# LocalizationBoard_B_1_0_Schematic_CG.net
KiCad netlist of a schematic drawn in Altium Designer
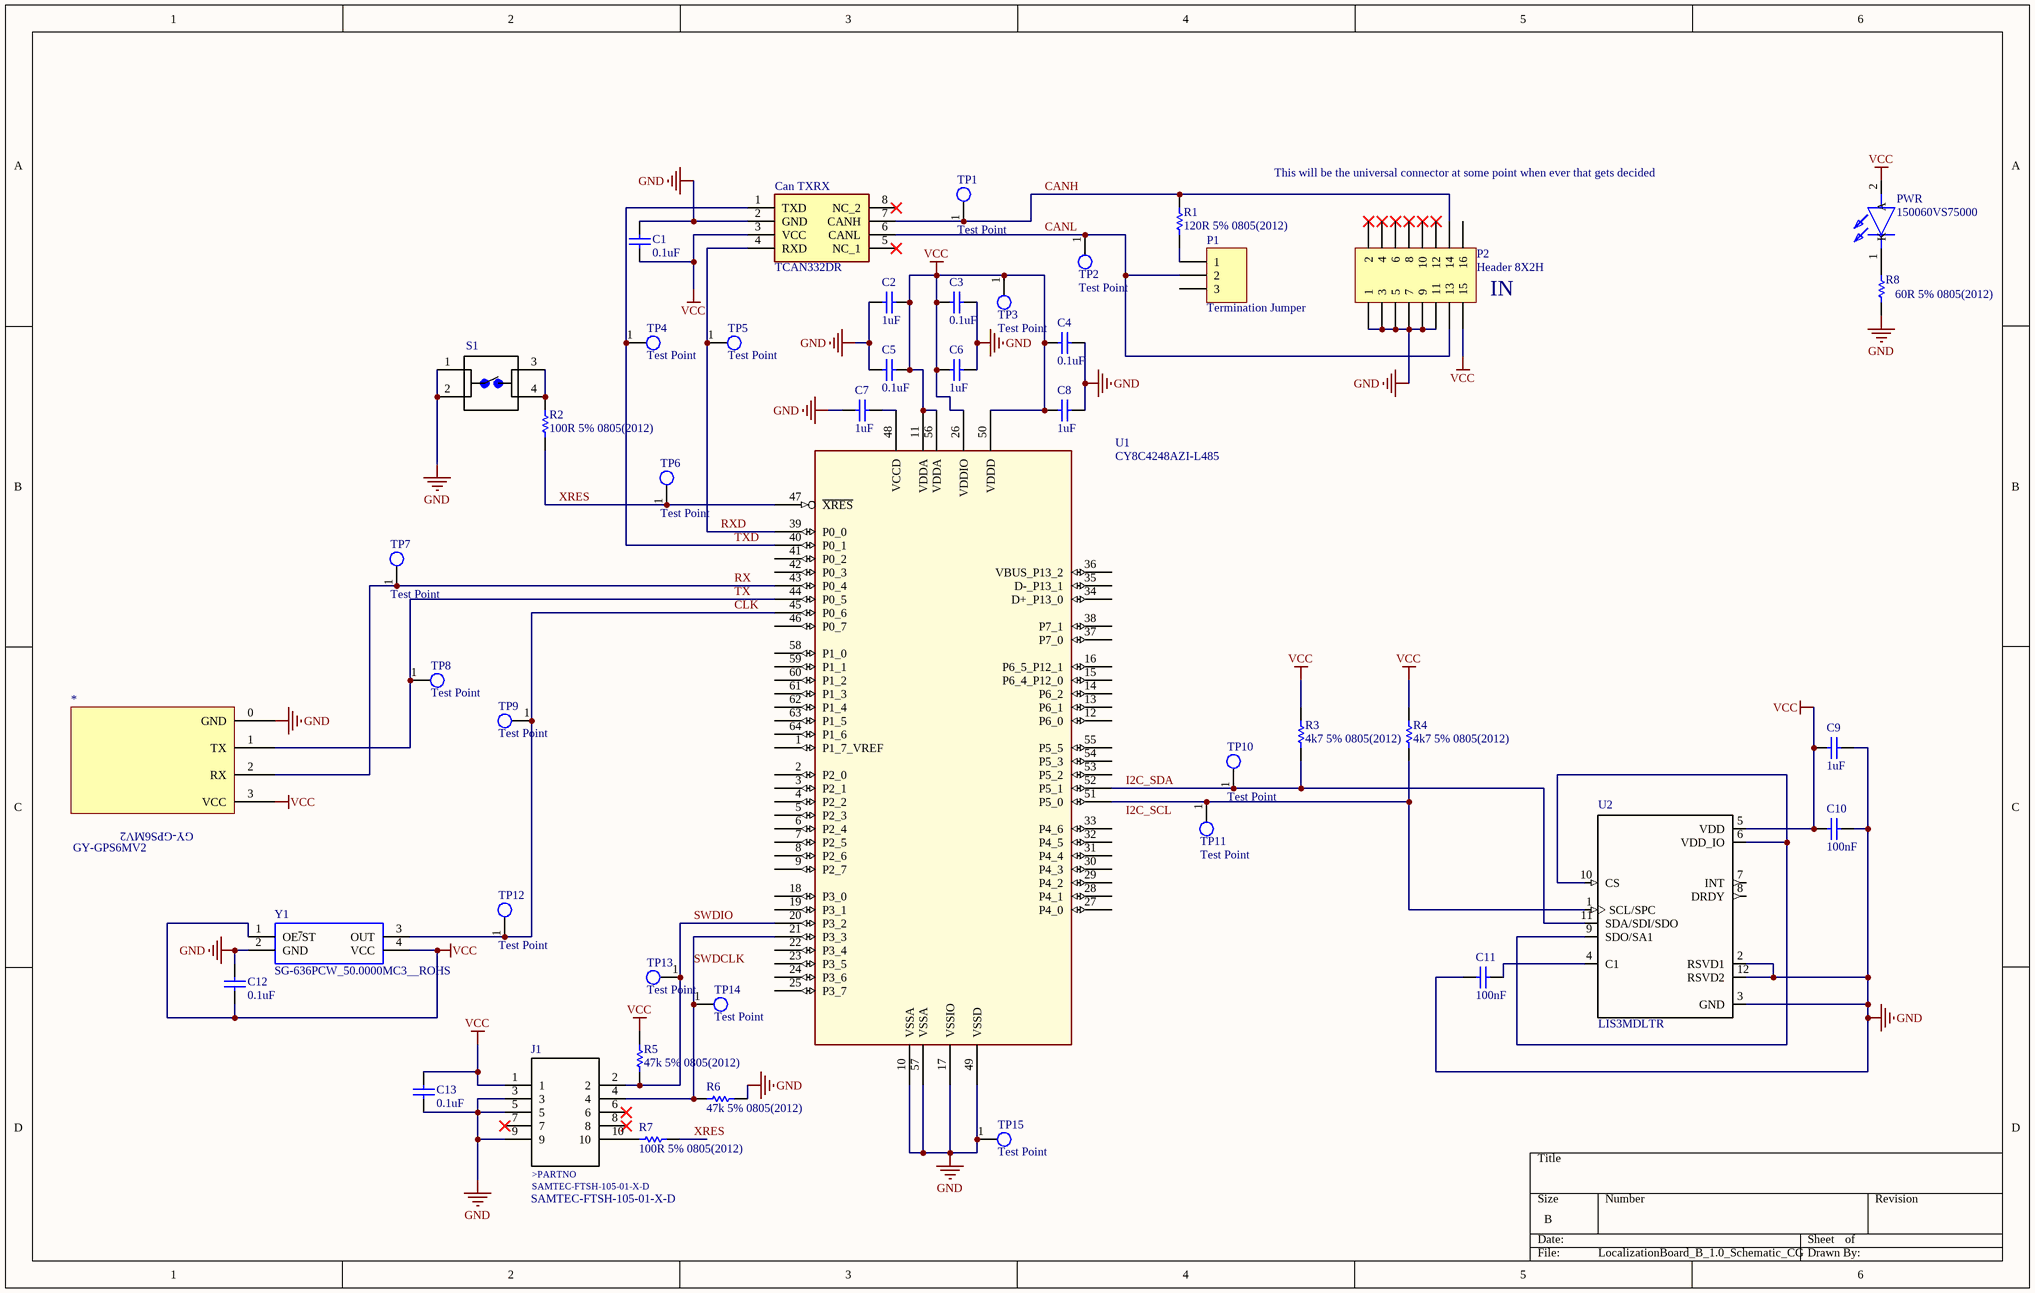
[diagram p0: LocalizationBoard_B_1.0_Schematic_CG.SchDoc]

(export (version "E")
  (design (tool "Eeschema 10.0.6"))
  (components
    (comp (ref "*")
      (value "GY-GPS6MV2")
      (footprint "GY-GPS6MV2")
      (libsource (lib "Husky Robotics Standard Library 2019-2020") (part "GY-GPS6MV2"))
    )
    (comp (ref "C1")
      (value "0.1uF")
      (footprint "CAPC2013X88X50ML20T25")
      (fields (field (name "PART NUMBER") "C0805C222M5RACTU") (field (name "MANUFACTURER") "Kemet"))
      (libsource (lib "Altium Content Vault") (part "CAP"))
    )
    (comp (ref "C2")
      (value "1uF")
      (footprint "CAPC2013X88X50ML20T25")
      (fields (field (name "PART NUMBER") "C0805C222M5RACTU") (field (name "MANUFACTURER") "Kemet"))
      (libsource (lib "Altium Content Vault") (part "CAP"))
    )
    (comp (ref "C3")
      (value "0.1uF")
      (footprint "CAPC2013X88X50ML20T25")
      (fields (field (name "PART NUMBER") "C0805C222M5RACTU") (field (name "MANUFACTURER") "Kemet"))
      (libsource (lib "Altium Content Vault") (part "CAP"))
    )
    (comp (ref "C4")
      (value "0.1uF")
      (footprint "CAPC2013X88X50ML20T25")
      (fields (field (name "PART NUMBER") "C0805C222M5RACTU") (field (name "MANUFACTURER") "Kemet"))
      (libsource (lib "Altium Content Vault") (part "CAP"))
    )
    (comp (ref "C5")
      (value "0.1uF")
      (footprint "CAPC2013X88X50ML20T25")
      (fields (field (name "PART NUMBER") "C0805C222M5RACTU") (field (name "MANUFACTURER") "Kemet"))
      (libsource (lib "Altium Content Vault") (part "CAP"))
    )
    (comp (ref "C6")
      (value "1uF")
      (footprint "CAPC2013X88X50ML20T25")
      (fields (field (name "PART NUMBER") "C0805C222M5RACTU") (field (name "MANUFACTURER") "Kemet"))
      (libsource (lib "Altium Content Vault") (part "CAP"))
    )
    (comp (ref "C7")
      (value "1uF")
      (footprint "CAPC2013X88X50ML20T25")
      (fields (field (name "PART NUMBER") "C0805C222M5RACTU") (field (name "MANUFACTURER") "Kemet"))
      (libsource (lib "Altium Content Vault") (part "CAP"))
    )
    (comp (ref "C8")
      (value "1uF")
      (footprint "CAPC2013X88X50ML20T25")
      (fields (field (name "PART NUMBER") "C0805C222M5RACTU") (field (name "MANUFACTURER") "Kemet"))
      (libsource (lib "Altium Content Vault") (part "CAP"))
    )
    (comp (ref "C9")
      (value "1uF")
      (footprint "CAPC2013X88X50ML20T25")
      (fields (field (name "PART NUMBER") "C0805C222M5RACTU") (field (name "MANUFACTURER") "Kemet"))
      (libsource (lib "Altium Content Vault") (part "CAP"))
    )
    (comp (ref "C10")
      (value "100nF")
      (footprint "CAPC2013X88X50ML20T25")
      (fields (field (name "PART NUMBER") "C0805C222M5RACTU") (field (name "MANUFACTURER") "Kemet"))
      (libsource (lib "Altium Content Vault") (part "CAP"))
    )
    (comp (ref "C11")
      (value "100nF")
      (footprint "CAPC2013X88X50ML20T25")
      (fields (field (name "PART NUMBER") "C0805C222M5RACTU") (field (name "MANUFACTURER") "Kemet"))
      (libsource (lib "Altium Content Vault") (part "CAP"))
    )
    (comp (ref "C12")
      (value "0.1uF")
      (footprint "CAPC2013X88X50ML20T25")
      (fields (field (name "PART NUMBER") "C0805C222M5RACTU") (field (name "MANUFACTURER") "Kemet"))
      (libsource (lib "Altium Content Vault") (part "CAP"))
    )
    (comp (ref "C13")
      (value "0.1uF")
      (footprint "CAPC2013X88X50ML20T25")
      (fields (field (name "PART NUMBER") "C0805C222M5RACTU") (field (name "MANUFACTURER") "Kemet"))
      (libsource (lib "Altium Content Vault") (part "CAP"))
    )
    (comp (ref "Can TXRX")
      (value "TCAN332DR")
      (footprint "SamacSys:SOIC127P600X175-8N")
      (description "Integrated Circuit")
      (fields (field (name "MOUSER PART NUMBER") "595-TCAN332DR"))
      (libsource (lib "*") (part "TCAN332DR"))
    )
    (comp (ref "J1")
      (value "SAMTEC-FTSH-105-01-X-D")
      (footprint "SAMTEC-FTSH-105-01-X-D")
      (libsource (lib "Husky Robotics Standard Library 2019-2020") (part "SAMTEC-FTSH-105-01-X-D"))
    )
    (comp (ref "P1")
      (value "Termination Jumper")
      (footprint "HDR1X3")
      (description "Header, 3-Pin")
      (fields (field (name "PUBLISHER") "Altium Limited"))
      (libsource (lib "Miscellaneous Connectors") (part "Header 3"))
    )
    (comp (ref "P2")
      (value "Header 8X2H")
      (footprint "HDR2X8H")
      (description "Header, 8-Pin, Dual row, Right Angle")
      (fields (field (name "PUBLISHER") "Altium Limited"))
      (libsource (lib "Miscellaneous Connectors") (part "Header 8X2H"))
    )
    (comp (ref "PWR")
      (value "150060VS75000")
      (footprint "SamacSys:LEDC1608X80N")
      (description "LED")
      (fields
        (field (name "MOUSER PART NUMBER") "710-150060VS75000")
        (field (name "RS PART NUMBER") "8154215P")
      )
      (libsource (lib "*") (part "150060VS75000"))
    )
    (comp (ref "R1")
      (value "120R 5% 0805(2012)")
      (footprint "RESC0805(2012)_N")
      (description "120R 0.125W 5% 0805 (2012 Metric)  SMD")
      (fields (field (name "TOLERANCE") "5 %") (field (name "POWER") "0.125 W"))
      (libsource (lib "Husky Robotics Standard Library 2019-2020") (part "120R 5% 0805"))
    )
    (comp (ref "R2")
      (value "100R 5% 0805(2012)")
      (footprint "RESC0805(2012)_N")
      (description "120R 0.125W 5% 0805 (2012 Metric)  SMD")
      (fields (field (name "TOLERANCE") "5 %") (field (name "POWER") "0.125 W"))
      (libsource (lib "Husky Robotics Standard Library 2019-2020") (part "120R 5% 0805"))
    )
    (comp (ref "R3")
      (value "4k7 5% 0805(2012)")
      (footprint "RESC0805(2012)_N")
      (description "120R 0.125W 5% 0805 (2012 Metric)  SMD")
      (fields (field (name "TOLERANCE") "5 %") (field (name "POWER") "0.125 W"))
      (libsource (lib "Husky Robotics Standard Library 2019-2020") (part "120R 5% 0805"))
    )
    (comp (ref "R4")
      (value "4k7 5% 0805(2012)")
      (footprint "RESC0805(2012)_N")
      (description "120R 0.125W 5% 0805 (2012 Metric)  SMD")
      (fields (field (name "TOLERANCE") "5 %") (field (name "POWER") "0.125 W"))
      (libsource (lib "Husky Robotics Standard Library 2019-2020") (part "120R 5% 0805"))
    )
    (comp (ref "R5")
      (value "47k 5% 0805(2012)")
      (footprint "RESC0805(2012)_N")
      (description "120R 0.125W 5% 0805 (2012 Metric)  SMD")
      (fields (field (name "TOLERANCE") "5 %") (field (name "POWER") "0.125 W"))
      (libsource (lib "Husky Robotics Standard Library 2019-2020") (part "120R 5% 0805"))
    )
    (comp (ref "R6")
      (value "47k 5% 0805(2012)")
      (footprint "RESC0805(2012)_N")
      (description "120R 0.125W 5% 0805 (2012 Metric)  SMD")
      (fields (field (name "TOLERANCE") "5 %") (field (name "POWER") "0.125 W"))
      (libsource (lib "Husky Robotics Standard Library 2019-2020") (part "120R 5% 0805"))
    )
    (comp (ref "R7")
      (value "100R 5% 0805(2012)")
      (footprint "RESC0805(2012)_N")
      (description "120R 0.125W 5% 0805 (2012 Metric)  SMD")
      (fields (field (name "TOLERANCE") "5 %") (field (name "POWER") "0.125 W"))
      (libsource (lib "Husky Robotics Standard Library 2019-2020") (part "120R 5% 0805"))
    )
    (comp (ref "R8")
      (value "60R 5% 0805(2012)")
      (footprint "RESC0805(2012)_N")
      (description "120R 0.125W 5% 0805 (2012 Metric)  SMD")
      (fields (field (name "TOLERANCE") "5 %") (field (name "POWER") "0.125 W"))
      (libsource (lib "Husky Robotics Standard Library 2019-2020") (part "120R 5% 0805"))
    )
    (comp (ref "S1")
      (value "1825910-7")
      (footprint "Switch 6mm 24V (NO)")
      (description "FSM4JAH=6MM TACT SWITCH, HIGH TEMP")
      (fields (field (name "MF") "TE Connectivity") (field (name "DIGI-KEY_PART_NUMBER") "450-1804-ND"))
      (libsource (lib "Husky Robotics Standard Library 2019-2020") (part "Switch 6mm 24V (NO)"))
    )
    (comp (ref "TP1")
      (value "Test Point")
      (footprint "Test Point Through-hole")
      (libsource (lib "Husky Robotics Standard Library 2019-2020") (part "Test Point"))
    )
    (comp (ref "TP2")
      (value "Test Point")
      (footprint "Test Point Through-hole")
      (libsource (lib "Husky Robotics Standard Library 2019-2020") (part "Test Point"))
    )
    (comp (ref "TP3")
      (value "Test Point")
      (footprint "Test Point Through-hole")
      (libsource (lib "Husky Robotics Standard Library 2019-2020") (part "Test Point"))
    )
    (comp (ref "TP4")
      (value "Test Point")
      (footprint "Test Point Through-hole")
      (libsource (lib "Husky Robotics Standard Library 2019-2020") (part "Test Point"))
    )
    (comp (ref "TP5")
      (value "Test Point")
      (footprint "Test Point Through-hole")
      (libsource (lib "Husky Robotics Standard Library 2019-2020") (part "Test Point"))
    )
    (comp (ref "TP6")
      (value "Test Point")
      (footprint "Test Point Through-hole")
      (libsource (lib "Husky Robotics Standard Library 2019-2020") (part "Test Point"))
    )
    (comp (ref "TP7")
      (value "Test Point")
      (footprint "Test Point Through-hole")
      (libsource (lib "Husky Robotics Standard Library 2019-2020") (part "Test Point"))
    )
    (comp (ref "TP8")
      (value "Test Point")
      (footprint "Test Point Through-hole")
      (libsource (lib "Husky Robotics Standard Library 2019-2020") (part "Test Point"))
    )
    (comp (ref "TP9")
      (value "Test Point")
      (footprint "Test Point Through-hole")
      (libsource (lib "Husky Robotics Standard Library 2019-2020") (part "Test Point"))
    )
    (comp (ref "TP10")
      (value "Test Point")
      (footprint "Test Point Through-hole")
      (libsource (lib "Husky Robotics Standard Library 2019-2020") (part "Test Point"))
    )
    (comp (ref "TP11")
      (value "Test Point")
      (footprint "Test Point Through-hole")
      (libsource (lib "Husky Robotics Standard Library 2019-2020") (part "Test Point"))
    )
    (comp (ref "TP12")
      (value "Test Point")
      (footprint "Test Point Through-hole")
      (libsource (lib "Husky Robotics Standard Library 2019-2020") (part "Test Point"))
    )
    (comp (ref "TP13")
      (value "Test Point")
      (footprint "Test Point Through-hole")
      (libsource (lib "Husky Robotics Standard Library 2019-2020") (part "Test Point"))
    )
    (comp (ref "TP14")
      (value "Test Point")
      (footprint "Test Point Through-hole")
      (libsource (lib "Husky Robotics Standard Library 2019-2020") (part "Test Point"))
    )
    (comp (ref "TP15")
      (value "Test Point")
      (footprint "Test Point Through-hole")
      (libsource (lib "Husky Robotics Standard Library 2019-2020") (part "Test Point"))
    )
    (comp (ref "U1")
      (value "CY8C4248AZI-L485")
      (footprint "TQFP50P1200X1200X160-64N")
      (libsource (lib "Husky Robotics Standard Library 2019-2020") (part "CY8C4248AZI-L485"))
    )
    (comp (ref "U2")
      (value "LIS3MDLTR")
      (footprint "*XDCR_LIS3MDLTR")
      (description "LIS3MDL Series 3 Axis Â±2/Â±8/Â±12/Â±16 g 3.6V High Performance Magnetometer LGA-12")
      (fields (field (name "DIGI-KEY_PART_NUMBER") "497-13892-1-ND") (field (name "MF") "STMicroelectronics"))
      (libsource (lib "LIS3MDLTR") (part "LIS3MDLTR"))
    )
    (comp (ref "Y1")
      (value "SG-636PCW_50.0000MC3__ROHS")
      (footprint "SG-636")
      (description "Standard Clock Oscillators 50MHz 3.3Volt 100ppm -20C +70C")
      (fields (field (name "MANUFACTURER_PART_NUMBER") "SG-636PCW 50.0000MC3: ROHS"))
      (libsource (lib "Husky Robotics Standard Library 2019-2020") (part "SG-636"))
    )
  )
  (nets
    (net (code "1") (name "/CANH") (class "Default")
      (node (ref "Can TXRX") (pin "7") (pinfunction "CANH_7") (pintype "passive"))
      (node (ref "P2") (pin "14") (pinfunction "14_14") (pintype "passive"))
      (node (ref "R1") (pin "2") (pinfunction "2_2") (pintype "passive"))
      (node (ref "TP1") (pin "1") (pinfunction "1_1") (pintype "passive"))
    )
    (net (code "2") (name "/CANL") (class "Default")
      (node (ref "Can TXRX") (pin "6") (pinfunction "CANL_6") (pintype "passive"))
      (node (ref "P1") (pin "2") (pinfunction "2_2") (pintype "passive"))
      (node (ref "P2") (pin "13") (pinfunction "13_13") (pintype "passive"))
      (node (ref "TP2") (pin "1") (pinfunction "1_1") (pintype "passive"))
    )
    (net (code "3") (name "/CLK") (class "Default")
      (node (ref "TP12") (pin "1") (pinfunction "1_1") (pintype "passive"))
      (node (ref "TP9") (pin "1") (pinfunction "1_1") (pintype "passive"))
      (node (ref "U1") (pin "45") (pinfunction "P0_6_45") (pintype "bidirectional"))
      (node (ref "Y1") (pin "3") (pinfunction "OUT_3") (pintype "passive"))
    )
    (net (code "4") (name "/I2C_SCL") (class "Default")
      (node (ref "R4") (pin "1") (pinfunction "1_1") (pintype "passive"))
      (node (ref "TP11") (pin "1") (pinfunction "1_1") (pintype "passive"))
      (node (ref "U1") (pin "51") (pinfunction "P5_0_51") (pintype "bidirectional"))
      (node (ref "U2") (pin "1") (pinfunction "SCL/SPC_1") (pintype "input"))
    )
    (net (code "5") (name "/I2C_SDA") (class "Default")
      (node (ref "R3") (pin "1") (pinfunction "1_1") (pintype "passive"))
      (node (ref "TP10") (pin "1") (pinfunction "1_1") (pintype "passive"))
      (node (ref "U1") (pin "52") (pinfunction "P5_1_52") (pintype "bidirectional"))
      (node (ref "U2") (pin "11") (pinfunction "SDA/SDI/SDO_11") (pintype "bidirectional"))
    )
    (net (code "6") (name "/RX") (class "Default")
      (node (ref "*") (pin "2") (pinfunction "RX_2") (pintype "passive"))
      (node (ref "TP7") (pin "1") (pinfunction "1_1") (pintype "passive"))
      (node (ref "U1") (pin "43") (pinfunction "P0_4_43") (pintype "bidirectional"))
    )
    (net (code "7") (name "/RXD") (class "Default")
      (node (ref "Can TXRX") (pin "4") (pinfunction "RXD_4") (pintype "passive"))
      (node (ref "TP5") (pin "1") (pinfunction "1_1") (pintype "passive"))
      (node (ref "U1") (pin "39") (pinfunction "P0_0_39") (pintype "bidirectional"))
    )
    (net (code "8") (name "/SWDCLK") (class "Default")
      (node (ref "J1") (pin "4") (pinfunction "4_4") (pintype "passive"))
      (node (ref "R6") (pin "1") (pinfunction "1_1") (pintype "passive"))
      (node (ref "TP14") (pin "1") (pinfunction "1_1") (pintype "passive"))
      (node (ref "U1") (pin "21") (pinfunction "P3_3_21") (pintype "bidirectional"))
    )
    (net (code "9") (name "/SWDIO") (class "Default")
      (node (ref "J1") (pin "2") (pinfunction "2_2") (pintype "passive"))
      (node (ref "R5") (pin "1") (pinfunction "1_1") (pintype "passive"))
      (node (ref "TP13") (pin "1") (pinfunction "1_1") (pintype "passive"))
      (node (ref "U1") (pin "20") (pinfunction "P3_2_20") (pintype "bidirectional"))
    )
    (net (code "10") (name "/TX") (class "Default")
      (node (ref "*") (pin "1") (pinfunction "TX_1") (pintype "passive"))
      (node (ref "TP8") (pin "1") (pinfunction "1_1") (pintype "passive"))
      (node (ref "U1") (pin "44") (pinfunction "P0_5_44") (pintype "bidirectional"))
    )
    (net (code "11") (name "/TXD") (class "Default")
      (node (ref "Can TXRX") (pin "1") (pinfunction "TXD_1") (pintype "passive"))
      (node (ref "TP4") (pin "1") (pinfunction "1_1") (pintype "passive"))
      (node (ref "U1") (pin "40") (pinfunction "P0_1_40") (pintype "bidirectional"))
    )
    (net (code "12") (name "/XRES") (class "Default")
      (node (ref "R2") (pin "1") (pinfunction "1_1") (pintype "passive"))
      (node (ref "R7") (pin "1") (pinfunction "1_1") (pintype "passive"))
      (node (ref "TP6") (pin "1") (pinfunction "1_1") (pintype "passive"))
      (node (ref "U1") (pin "47") (pinfunction "~{XRES}_47") (pintype "input"))
    )
    (net (code "13") (name "GND") (class "Default")
      (node (ref "*") (pin "0") (pinfunction "GND_0") (pintype "passive"))
      (node (ref "C1") (pin "2") (pinfunction "2_2") (pintype "passive"))
      (node (ref "C10") (pin "2") (pinfunction "2_2") (pintype "passive"))
      (node (ref "C11") (pin "1") (pinfunction "1_1") (pintype "passive"))
      (node (ref "C12") (pin "2") (pinfunction "2_2") (pintype "passive"))
      (node (ref "C13") (pin "2") (pinfunction "2_2") (pintype "passive"))
      (node (ref "C2") (pin "1") (pinfunction "1_1") (pintype "passive"))
      (node (ref "C3") (pin "2") (pinfunction "2_2") (pintype "passive"))
      (node (ref "C4") (pin "2") (pinfunction "2_2") (pintype "passive"))
      (node (ref "C5") (pin "1") (pinfunction "1_1") (pintype "passive"))
      (node (ref "C6") (pin "2") (pinfunction "2_2") (pintype "passive"))
      (node (ref "C7") (pin "1") (pinfunction "1_1") (pintype "passive"))
      (node (ref "C8") (pin "2") (pinfunction "2_2") (pintype "passive"))
      (node (ref "C9") (pin "2") (pinfunction "2_2") (pintype "passive"))
      (node (ref "Can TXRX") (pin "2") (pinfunction "GND_2") (pintype "passive"))
      (node (ref "J1") (pin "3") (pinfunction "3_3") (pintype "passive"))
      (node (ref "J1") (pin "5") (pinfunction "5_5") (pintype "passive"))
      (node (ref "J1") (pin "9") (pinfunction "9_9") (pintype "passive"))
      (node (ref "P2") (pin "1") (pinfunction "1_1") (pintype "passive"))
      (node (ref "P2") (pin "11") (pinfunction "11_11") (pintype "passive"))
      (node (ref "P2") (pin "3") (pinfunction "3_3") (pintype "passive"))
      (node (ref "P2") (pin "5") (pinfunction "5_5") (pintype "passive"))
      (node (ref "P2") (pin "7") (pinfunction "7_7") (pintype "passive"))
      (node (ref "P2") (pin "9") (pinfunction "9_9") (pintype "passive"))
      (node (ref "R6") (pin "2") (pinfunction "2_2") (pintype "passive"))
      (node (ref "R8") (pin "1") (pinfunction "1_1") (pintype "passive"))
      (node (ref "S1") (pin "1") (pinfunction "1_1") (pintype "passive"))
      (node (ref "S1") (pin "2") (pinfunction "2_2") (pintype "passive"))
      (node (ref "TP15") (pin "1") (pinfunction "1_1") (pintype "passive"))
      (node (ref "U1") (pin "10") (pinfunction "VSSA_10") (pintype "power_in"))
      (node (ref "U1") (pin "17") (pinfunction "VSSIO_17") (pintype "power_in"))
      (node (ref "U1") (pin "49") (pinfunction "VSSD_49") (pintype "power_in"))
      (node (ref "U1") (pin "57") (pinfunction "VSSA_57") (pintype "power_in"))
      (node (ref "U2") (pin "12") (pinfunction "RSVD2_12") (pintype "passive"))
      (node (ref "U2") (pin "2") (pinfunction "RSVD1_2") (pintype "passive"))
      (node (ref "U2") (pin "3") (pinfunction "GND_3") (pintype "power_in"))
      (node (ref "Y1") (pin "2") (pinfunction "GND_2") (pintype "passive"))
    )
    (net (code "14") (name "Net-(J1-Pad10)") (class "Default")
      (node (ref "J1") (pin "10") (pinfunction "10_10") (pintype "passive"))
      (node (ref "R7") (pin "2") (pinfunction "2_2") (pintype "passive"))
    )
    (net (code "15") (name "Net-(P1-Pad1)") (class "Default")
      (node (ref "P1") (pin "1") (pinfunction "1_1") (pintype "passive"))
      (node (ref "R1") (pin "1") (pinfunction "1_1") (pintype "passive"))
    )
    (net (code "16") (name "Net-(PWR-K)") (class "Default")
      (node (ref "PWR") (pin "1") (pinfunction "K_1") (pintype "passive"))
      (node (ref "R8") (pin "2") (pinfunction "2_2") (pintype "passive"))
    )
    (net (code "17") (name "Net-(R2-Pad2)") (class "Default")
      (node (ref "R2") (pin "2") (pinfunction "2_2") (pintype "passive"))
      (node (ref "S1") (pin "3") (pinfunction "3_3") (pintype "passive"))
      (node (ref "S1") (pin "4") (pinfunction "4_4") (pintype "passive"))
    )
    (net (code "18") (name "Net-(U1-VCCD)") (class "Default")
      (node (ref "C7") (pin "2") (pinfunction "2_2") (pintype "passive"))
      (node (ref "U1") (pin "48") (pinfunction "VCCD_48") (pintype "power_in"))
    )
    (net (code "19") (name "Net-(U2-C1)") (class "Default")
      (node (ref "C11") (pin "2") (pinfunction "2_2") (pintype "passive"))
      (node (ref "U2") (pin "4") (pinfunction "C1_4") (pintype "passive"))
    )
    (net (code "20") (name "Net-(U2-CS)") (class "Default")
      (node (ref "U2") (pin "10") (pinfunction "CS_10") (pintype "input"))
      (node (ref "U2") (pin "6") (pinfunction "VDD_IO_6") (pintype "power_in"))
      (node (ref "U2") (pin "9") (pinfunction "SDO/SA1_9") (pintype "bidirectional"))
    )
    (net (code "21") (name "VCC") (class "Default")
      (node (ref "*") (pin "3") (pinfunction "VCC_3") (pintype "passive"))
      (node (ref "C1") (pin "1") (pinfunction "1_1") (pintype "passive"))
      (node (ref "C10") (pin "1") (pinfunction "1_1") (pintype "passive"))
      (node (ref "C12") (pin "1") (pinfunction "1_1") (pintype "passive"))
      (node (ref "C13") (pin "1") (pinfunction "1_1") (pintype "passive"))
      (node (ref "C2") (pin "2") (pinfunction "2_2") (pintype "passive"))
      (node (ref "C3") (pin "1") (pinfunction "1_1") (pintype "passive"))
      (node (ref "C4") (pin "1") (pinfunction "1_1") (pintype "passive"))
      (node (ref "C5") (pin "2") (pinfunction "2_2") (pintype "passive"))
      (node (ref "C6") (pin "1") (pinfunction "1_1") (pintype "passive"))
      (node (ref "C8") (pin "1") (pinfunction "1_1") (pintype "passive"))
      (node (ref "C9") (pin "1") (pinfunction "1_1") (pintype "passive"))
      (node (ref "Can TXRX") (pin "3") (pinfunction "VCC_3") (pintype "passive"))
      (node (ref "J1") (pin "1") (pinfunction "1_1") (pintype "passive"))
      (node (ref "P2") (pin "15") (pinfunction "15_15") (pintype "passive"))
      (node (ref "PWR") (pin "2") (pinfunction "A_2") (pintype "passive"))
      (node (ref "R3") (pin "2") (pinfunction "2_2") (pintype "passive"))
      (node (ref "R4") (pin "2") (pinfunction "2_2") (pintype "passive"))
      (node (ref "R5") (pin "2") (pinfunction "2_2") (pintype "passive"))
      (node (ref "TP3") (pin "1") (pinfunction "1_1") (pintype "passive"))
      (node (ref "U1") (pin "11") (pinfunction "VDDA_11") (pintype "power_in"))
      (node (ref "U1") (pin "26") (pinfunction "VDDIO_26") (pintype "power_in"))
      (node (ref "U1") (pin "50") (pinfunction "VDDD_50") (pintype "power_in"))
      (node (ref "U1") (pin "56") (pinfunction "VDDA_56") (pintype "power_in"))
      (node (ref "U2") (pin "5") (pinfunction "VDD_5") (pintype "power_in"))
      (node (ref "Y1") (pin "1") (pinfunction "OE~{/}ST_1") (pintype "passive"))
      (node (ref "Y1") (pin "4") (pinfunction "VCC_4") (pintype "power_in"))
    )
    (net (code "22") (name "unconnected-(Can TXRX-NC_1-Pad5)") (class "Default")
      (node (ref "Can TXRX") (pin "5") (pinfunction "NC_1_5") (pintype "passive+no_connect"))
    )
    (net (code "23") (name "unconnected-(Can TXRX-NC_2-Pad8)") (class "Default")
      (node (ref "Can TXRX") (pin "8") (pinfunction "NC_2_8") (pintype "passive+no_connect"))
    )
    (net (code "24") (name "unconnected-(J1-Pad6)") (class "Default")
      (node (ref "J1") (pin "6") (pinfunction "6_6") (pintype "passive+no_connect"))
    )
    (net (code "25") (name "unconnected-(J1-Pad7)") (class "Default")
      (node (ref "J1") (pin "7") (pinfunction "7_7") (pintype "passive+no_connect"))
    )
    (net (code "26") (name "unconnected-(J1-Pad8)") (class "Default")
      (node (ref "J1") (pin "8") (pinfunction "8_8") (pintype "passive+no_connect"))
    )
    (net (code "27") (name "unconnected-(P1-Pad3)") (class "Default")
      (node (ref "P1") (pin "3") (pinfunction "3_3") (pintype "passive"))
    )
    (net (code "28") (name "unconnected-(P2-Pad2)") (class "Default")
      (node (ref "P2") (pin "2") (pinfunction "2_2") (pintype "passive+no_connect"))
    )
    (net (code "29") (name "unconnected-(P2-Pad4)") (class "Default")
      (node (ref "P2") (pin "4") (pinfunction "4_4") (pintype "passive+no_connect"))
    )
    (net (code "30") (name "unconnected-(P2-Pad6)") (class "Default")
      (node (ref "P2") (pin "6") (pinfunction "6_6") (pintype "passive+no_connect"))
    )
    (net (code "31") (name "unconnected-(P2-Pad8)") (class "Default")
      (node (ref "P2") (pin "8") (pinfunction "8_8") (pintype "passive+no_connect"))
    )
    (net (code "32") (name "unconnected-(P2-Pad10)") (class "Default")
      (node (ref "P2") (pin "10") (pinfunction "10_10") (pintype "passive+no_connect"))
    )
    (net (code "33") (name "unconnected-(P2-Pad12)") (class "Default")
      (node (ref "P2") (pin "12") (pinfunction "12_12") (pintype "passive+no_connect"))
    )
    (net (code "34") (name "unconnected-(P2-Pad16)") (class "Default")
      (node (ref "P2") (pin "16") (pinfunction "16_16") (pintype "passive"))
    )
    (net (code "35") (name "unconnected-(U1-D+_P13_0-Pad34)") (class "Default")
      (node (ref "U1") (pin "34") (pinfunction "D+_P13_0_34") (pintype "bidirectional"))
    )
    (net (code "36") (name "unconnected-(U1-D-_P13_1-Pad35)") (class "Default")
      (node (ref "U1") (pin "35") (pinfunction "D-_P13_1_35") (pintype "bidirectional"))
    )
    (net (code "37") (name "unconnected-(U1-P0_2-Pad41)") (class "Default")
      (node (ref "U1") (pin "41") (pinfunction "P0_2_41") (pintype "bidirectional"))
    )
    (net (code "38") (name "unconnected-(U1-P0_3-Pad42)") (class "Default")
      (node (ref "U1") (pin "42") (pinfunction "P0_3_42") (pintype "bidirectional"))
    )
    (net (code "39") (name "unconnected-(U1-P0_7-Pad46)") (class "Default")
      (node (ref "U1") (pin "46") (pinfunction "P0_7_46") (pintype "bidirectional"))
    )
    (net (code "40") (name "unconnected-(U1-P1_0-Pad58)") (class "Default")
      (node (ref "U1") (pin "58") (pinfunction "P1_0_58") (pintype "bidirectional"))
    )
    (net (code "41") (name "unconnected-(U1-P1_1-Pad59)") (class "Default")
      (node (ref "U1") (pin "59") (pinfunction "P1_1_59") (pintype "bidirectional"))
    )
    (net (code "42") (name "unconnected-(U1-P1_2-Pad60)") (class "Default")
      (node (ref "U1") (pin "60") (pinfunction "P1_2_60") (pintype "bidirectional"))
    )
    (net (code "43") (name "unconnected-(U1-P1_3-Pad61)") (class "Default")
      (node (ref "U1") (pin "61") (pinfunction "P1_3_61") (pintype "bidirectional"))
    )
    (net (code "44") (name "unconnected-(U1-P1_4-Pad62)") (class "Default")
      (node (ref "U1") (pin "62") (pinfunction "P1_4_62") (pintype "bidirectional"))
    )
    (net (code "45") (name "unconnected-(U1-P1_5-Pad63)") (class "Default")
      (node (ref "U1") (pin "63") (pinfunction "P1_5_63") (pintype "bidirectional"))
    )
    (net (code "46") (name "unconnected-(U1-P1_6-Pad64)") (class "Default")
      (node (ref "U1") (pin "64") (pinfunction "P1_6_64") (pintype "bidirectional"))
    )
    (net (code "47") (name "unconnected-(U1-P1_7_VREF-Pad1)") (class "Default")
      (node (ref "U1") (pin "1") (pinfunction "P1_7_VREF_1") (pintype "bidirectional"))
    )
    (net (code "48") (name "unconnected-(U1-P2_0-Pad2)") (class "Default")
      (node (ref "U1") (pin "2") (pinfunction "P2_0_2") (pintype "bidirectional"))
    )
    (net (code "49") (name "unconnected-(U1-P2_1-Pad3)") (class "Default")
      (node (ref "U1") (pin "3") (pinfunction "P2_1_3") (pintype "bidirectional"))
    )
    (net (code "50") (name "unconnected-(U1-P2_2-Pad4)") (class "Default")
      (node (ref "U1") (pin "4") (pinfunction "P2_2_4") (pintype "bidirectional"))
    )
    (net (code "51") (name "unconnected-(U1-P2_3-Pad5)") (class "Default")
      (node (ref "U1") (pin "5") (pinfunction "P2_3_5") (pintype "bidirectional"))
    )
    (net (code "52") (name "unconnected-(U1-P2_4-Pad6)") (class "Default")
      (node (ref "U1") (pin "6") (pinfunction "P2_4_6") (pintype "bidirectional"))
    )
    (net (code "53") (name "unconnected-(U1-P2_5-Pad7)") (class "Default")
      (node (ref "U1") (pin "7") (pinfunction "P2_5_7") (pintype "bidirectional"))
    )
    (net (code "54") (name "unconnected-(U1-P2_6-Pad8)") (class "Default")
      (node (ref "U1") (pin "8") (pinfunction "P2_6_8") (pintype "bidirectional"))
    )
    (net (code "55") (name "unconnected-(U1-P2_7-Pad9)") (class "Default")
      (node (ref "U1") (pin "9") (pinfunction "P2_7_9") (pintype "bidirectional"))
    )
    (net (code "56") (name "unconnected-(U1-P3_0-Pad18)") (class "Default")
      (node (ref "U1") (pin "18") (pinfunction "P3_0_18") (pintype "bidirectional"))
    )
    (net (code "57") (name "unconnected-(U1-P3_1-Pad19)") (class "Default")
      (node (ref "U1") (pin "19") (pinfunction "P3_1_19") (pintype "bidirectional"))
    )
    (net (code "58") (name "unconnected-(U1-P3_4-Pad22)") (class "Default")
      (node (ref "U1") (pin "22") (pinfunction "P3_4_22") (pintype "bidirectional"))
    )
    (net (code "59") (name "unconnected-(U1-P3_5-Pad23)") (class "Default")
      (node (ref "U1") (pin "23") (pinfunction "P3_5_23") (pintype "bidirectional"))
    )
    (net (code "60") (name "unconnected-(U1-P3_6-Pad24)") (class "Default")
      (node (ref "U1") (pin "24") (pinfunction "P3_6_24") (pintype "bidirectional"))
    )
    (net (code "61") (name "unconnected-(U1-P3_7-Pad25)") (class "Default")
      (node (ref "U1") (pin "25") (pinfunction "P3_7_25") (pintype "bidirectional"))
    )
    (net (code "62") (name "unconnected-(U1-P4_0-Pad27)") (class "Default")
      (node (ref "U1") (pin "27") (pinfunction "P4_0_27") (pintype "bidirectional"))
    )
    (net (code "63") (name "unconnected-(U1-P4_1-Pad28)") (class "Default")
      (node (ref "U1") (pin "28") (pinfunction "P4_1_28") (pintype "bidirectional"))
    )
    (net (code "64") (name "unconnected-(U1-P4_2-Pad29)") (class "Default")
      (node (ref "U1") (pin "29") (pinfunction "P4_2_29") (pintype "bidirectional"))
    )
    (net (code "65") (name "unconnected-(U1-P4_3-Pad30)") (class "Default")
      (node (ref "U1") (pin "30") (pinfunction "P4_3_30") (pintype "bidirectional"))
    )
    (net (code "66") (name "unconnected-(U1-P4_4-Pad31)") (class "Default")
      (node (ref "U1") (pin "31") (pinfunction "P4_4_31") (pintype "bidirectional"))
    )
    (net (code "67") (name "unconnected-(U1-P4_5-Pad32)") (class "Default")
      (node (ref "U1") (pin "32") (pinfunction "P4_5_32") (pintype "bidirectional"))
    )
    (net (code "68") (name "unconnected-(U1-P4_6-Pad33)") (class "Default")
      (node (ref "U1") (pin "33") (pinfunction "P4_6_33") (pintype "bidirectional"))
    )
    (net (code "69") (name "unconnected-(U1-P5_2-Pad53)") (class "Default")
      (node (ref "U1") (pin "53") (pinfunction "P5_2_53") (pintype "bidirectional"))
    )
    (net (code "70") (name "unconnected-(U1-P5_3-Pad54)") (class "Default")
      (node (ref "U1") (pin "54") (pinfunction "P5_3_54") (pintype "bidirectional"))
    )
    (net (code "71") (name "unconnected-(U1-P5_5-Pad55)") (class "Default")
      (node (ref "U1") (pin "55") (pinfunction "P5_5_55") (pintype "bidirectional"))
    )
    (net (code "72") (name "unconnected-(U1-P6_0-Pad12)") (class "Default")
      (node (ref "U1") (pin "12") (pinfunction "P6_0_12") (pintype "bidirectional"))
    )
    (net (code "73") (name "unconnected-(U1-P6_1-Pad13)") (class "Default")
      (node (ref "U1") (pin "13") (pinfunction "P6_1_13") (pintype "bidirectional"))
    )
    (net (code "74") (name "unconnected-(U1-P6_2-Pad14)") (class "Default")
      (node (ref "U1") (pin "14") (pinfunction "P6_2_14") (pintype "bidirectional"))
    )
    (net (code "75") (name "unconnected-(U1-P6_4_P12_0-Pad15)") (class "Default")
      (node (ref "U1") (pin "15") (pinfunction "P6_4_P12_0_15") (pintype "bidirectional"))
    )
    (net (code "76") (name "unconnected-(U1-P6_5_P12_1-Pad16)") (class "Default")
      (node (ref "U1") (pin "16") (pinfunction "P6_5_P12_1_16") (pintype "bidirectional"))
    )
    (net (code "77") (name "unconnected-(U1-P7_0-Pad37)") (class "Default")
      (node (ref "U1") (pin "37") (pinfunction "P7_0_37") (pintype "bidirectional"))
    )
    (net (code "78") (name "unconnected-(U1-P7_1-Pad38)") (class "Default")
      (node (ref "U1") (pin "38") (pinfunction "P7_1_38") (pintype "bidirectional"))
    )
    (net (code "79") (name "unconnected-(U1-VBUS_P13_2-Pad36)") (class "Default")
      (node (ref "U1") (pin "36") (pinfunction "VBUS_P13_2_36") (pintype "bidirectional"))
    )
    (net (code "80") (name "unconnected-(U2-DRDY-Pad8)") (class "Default")
      (node (ref "U2") (pin "8") (pinfunction "DRDY_8") (pintype "output"))
    )
    (net (code "81") (name "unconnected-(U2-INT-Pad7)") (class "Default")
      (node (ref "U2") (pin "7") (pinfunction "INT_7") (pintype "output"))
    )
  )
)
